# USB.net
KiCad netlist of a schematic drawn in Altium Designer
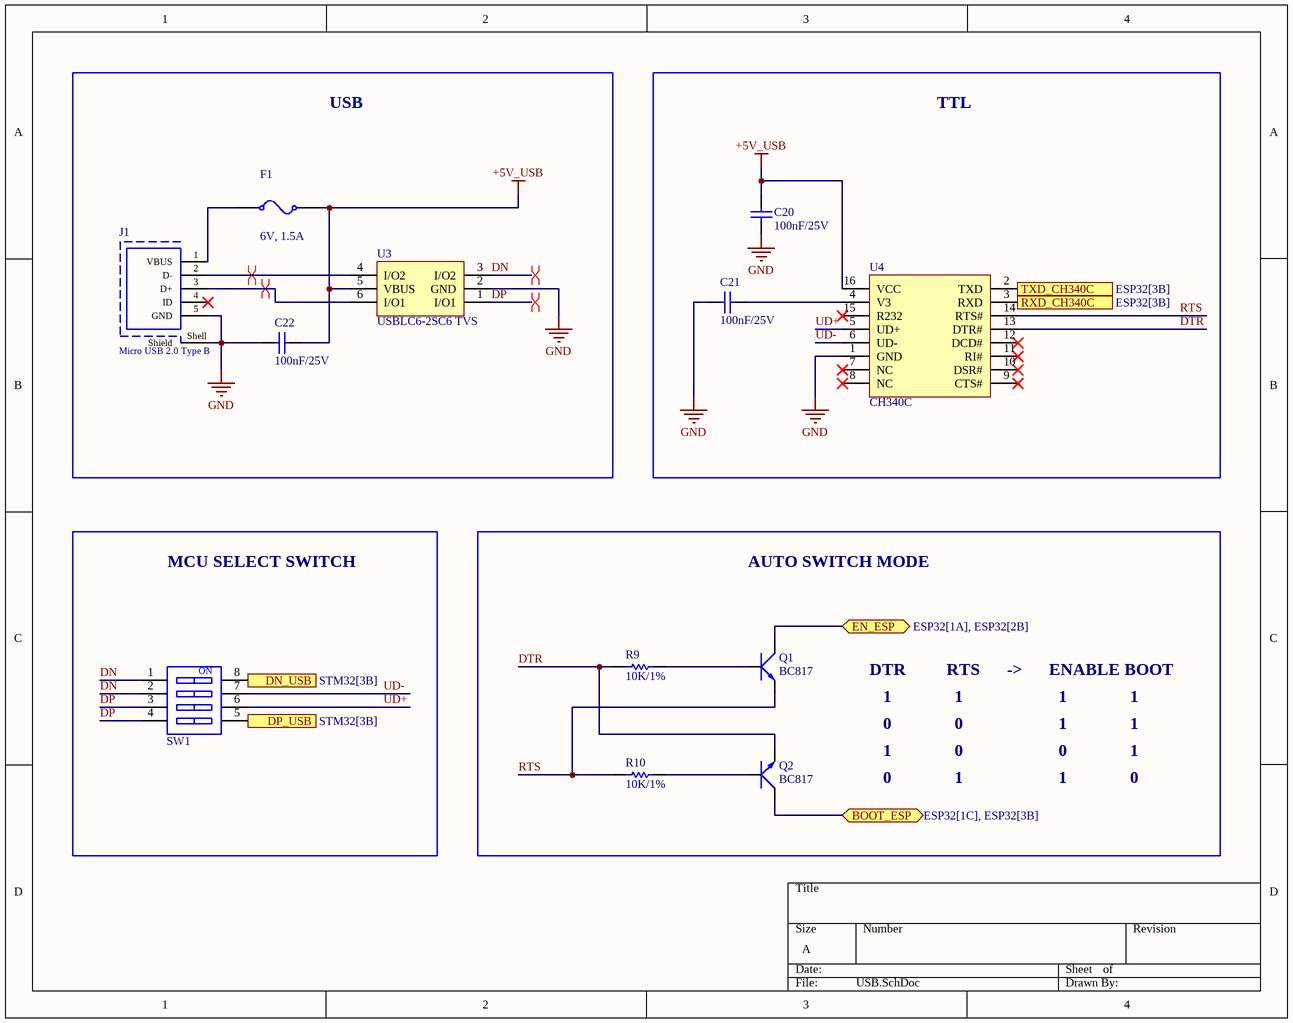
[diagram p0: USB.SchDoc]

(export (version "E")
  (design (tool "Eeschema 10.0.6"))
  (components
    (comp (ref "C20")
      (value "100nF/25V")
      (footprint "CAP-SM-0805")
      (description "Capacitor")
      (fields (field (name "Comment") "Cap Non-Pol SMD"))
      (libsource (lib "PIF_Library") (part "Cap Non-Pol SMD"))
    )
    (comp (ref "C21")
      (value "100nF/25V")
      (footprint "CAP-SM-0805")
      (description "Capacitor")
      (fields (field (name "Comment") "Cap Non-Pol SMD"))
      (libsource (lib "PIF_Library") (part "Cap Non-Pol SMD"))
    )
    (comp (ref "C22")
      (value "100nF/25V")
      (footprint "CAP-SM-0805")
      (description "Capacitor")
      (fields (field (name "Comment") "Cap Non-Pol SMD"))
      (libsource (lib "PIF_Library") (part "Cap Non-Pol SMD"))
    )
    (comp (ref "F1")
      (value "6V, 1.5A")
      (footprint "Fuse_SMD_1812")
      (description "Resettable Fuse, Size 1812, 24V, 1.5A")
      (fields (field (name "MANUFACTURER") "Littelfuse"))
      (libsource (lib "Altium_Fuse") (part "061812150024"))
    )
    (comp (ref "J1")
      (value "Micro USB 2.0 Type B")
      (footprint "629105150521")
      (description "Micro USB 2.0 Type B Receptacle WR-COM, Horizontal, SMT, with Pegs, High Current at Pin 1 & Pin 5")
      (fields (field (name "PART NUMBER") "629105150521") (field (name "PUBLISHER") "Wurth Elektronik"))
      (libsource (lib "Altium_USB") (part "629105150521"))
    )
    (comp (ref "Q1")
      (value "BC817")
      (footprint "SOT-23")
      (description "SOT-23 - C8658")
      (libsource (lib "Altium_Lib_by_KhueNguyenCreator") (part "Trans BC817"))
    )
    (comp (ref "Q2")
      (value "BC817")
      (footprint "SOT-23")
      (description "SOT-23 - C8658")
      (libsource (lib "Altium_Lib_by_KhueNguyenCreator") (part "Trans BC817"))
    )
    (comp (ref "R9")
      (value "10K/1%")
      (footprint "RES-SM-0805")
      (description "Resistor")
      (fields (field (name "Comment") "RESISTOR SMD"))
      (libsource (lib "PIF_Library") (part "RESISTOR SMD"))
    )
    (comp (ref "R10")
      (value "10K/1%")
      (footprint "RES-SM-0805")
      (description "Resistor")
      (fields (field (name "Comment") "RESISTOR SMD"))
      (libsource (lib "PIF_Library") (part "RESISTOR SMD"))
    )
    (comp (ref "SW1")
      (value "418117270904")
      (footprint "418117270904")
      (description "WS-DITV Compact THT Dip Switch, Raised Actuator, pitch 2.54mm, 4p")
      (fields (field (name "MANUFACTURER") "Wurth Elektronik"))
      (libsource (lib "Altium_Button") (part "418117270904"))
    )
    (comp (ref "U3")
      (value "USBLC6-2SC6 TVS")
      (footprint "SOT23-6")
      (description "Oscillator, Silicon IC 3.81Hz ~ 1MHz TSOT-23-6")
      (fields
        (field (name "MANUFACTURER") "Linear Technology/Analog Devices")
        (field (name "MANUFACTURER PART NUMBER") "LTC6992IS6-1")
      )
      (libsource (lib "Altium_Lib_by_KhueNguyenCreator") (part "IC_LTC6992IS6-1"))
    )
    (comp (ref "U4")
      (value "CH340C")
      (footprint "SOIC16_50_284_25X90_SMT")
      (description "USB Bridge, USB to UART USB 2.0 UART Interface")
      (fields (field (name "MANUFACTURER") "Olimex"))
      (libsource (lib "Altium_Lib_by_KhueNguyenCreator") (part "CH340C"))
    )
  )
  (nets
    (net (code "1") (name "+5V_USB") (class "Default")
      (node (ref "C20") (pin "1") (pinfunction "1_1") (pintype "passive"))
      (node (ref "C22") (pin "2") (pinfunction "2_2") (pintype "passive"))
      (node (ref "F1") (pin "1") (pinfunction "1_1") (pintype "passive"))
      (node (ref "U3") (pin "5") (pinfunction "VBUS_5") (pintype "passive"))
      (node (ref "U4") (pin "16") (pinfunction "VCC_16") (pintype "passive"))
    )
    (net (code "2") (name "/BOOT_ESP") (class "Default")
      (node (ref "Q2") (pin "3") (pinfunction "C_3") (pintype "passive"))
    )
    (net (code "3") (name "/DN") (class "Default")
      (node (ref "SW1") (pin "1") (pinfunction "1_1") (pintype "passive"))
      (node (ref "SW1") (pin "2") (pinfunction "2_2") (pintype "passive"))
      (node (ref "U3") (pin "3") (pinfunction "I/O2_3") (pintype "passive"))
    )
    (net (code "4") (name "/DN_USB") (class "Default")
      (node (ref "SW1") (pin "8") (pinfunction "8_8") (pintype "passive"))
    )
    (net (code "5") (name "/DP") (class "Default")
      (node (ref "SW1") (pin "3") (pinfunction "3_3") (pintype "passive"))
      (node (ref "SW1") (pin "4") (pinfunction "4_4") (pintype "passive"))
      (node (ref "U3") (pin "1") (pinfunction "I/O1_1") (pintype "passive"))
    )
    (net (code "6") (name "/DP_USB") (class "Default")
      (node (ref "SW1") (pin "5") (pinfunction "5_5") (pintype "passive"))
    )
    (net (code "7") (name "/DTR") (class "Default")
      (node (ref "Q2") (pin "2") (pinfunction "E_2") (pintype "passive"))
      (node (ref "R9") (pin "1") (pinfunction "1_1") (pintype "passive"))
      (node (ref "U4") (pin "13") (pinfunction "DTR#_13") (pintype "passive"))
    )
    (net (code "8") (name "/EN_ESP") (class "Default")
      (node (ref "Q1") (pin "3") (pinfunction "C_3") (pintype "passive"))
    )
    (net (code "9") (name "/RTS") (class "Default")
      (node (ref "Q1") (pin "2") (pinfunction "E_2") (pintype "passive"))
      (node (ref "R10") (pin "1") (pinfunction "1_1") (pintype "passive"))
      (node (ref "U4") (pin "14") (pinfunction "RTS#_14") (pintype "passive"))
    )
    (net (code "10") (name "/RXD_CH340C") (class "Default")
      (node (ref "U4") (pin "3") (pinfunction "RXD_3") (pintype "passive"))
    )
    (net (code "11") (name "/TXD_CH340C") (class "Default")
      (node (ref "U4") (pin "2") (pinfunction "TXD_2") (pintype "passive"))
    )
    (net (code "12") (name "/UD+") (class "Default")
      (node (ref "SW1") (pin "6") (pinfunction "6_6") (pintype "passive"))
      (node (ref "U4") (pin "5") (pinfunction "UD+_5") (pintype "passive"))
    )
    (net (code "13") (name "/UD-") (class "Default")
      (node (ref "SW1") (pin "7") (pinfunction "7_7") (pintype "passive"))
      (node (ref "U4") (pin "6") (pinfunction "UD-_6") (pintype "passive"))
    )
    (net (code "14") (name "GND") (class "Default")
      (node (ref "C20") (pin "2") (pinfunction "2_2") (pintype "passive"))
      (node (ref "C21") (pin "2") (pinfunction "2_2") (pintype "passive"))
      (node (ref "C22") (pin "1") (pinfunction "1_1") (pintype "passive"))
      (node (ref "J1") (pin "5") (pinfunction "GND_5") (pintype "passive"))
      (node (ref "J1") (pin "Shell") (pinfunction "Shield_Shell") (pintype "passive"))
      (node (ref "U3") (pin "2") (pinfunction "GND_2") (pintype "passive"))
      (node (ref "U4") (pin "1") (pinfunction "GND_1") (pintype "passive"))
    )
    (net (code "15") (name "Net-(J1-D+)") (class "Default")
      (node (ref "J1") (pin "3") (pinfunction "D+_3") (pintype "passive"))
      (node (ref "U3") (pin "6") (pinfunction "I/O1_6") (pintype "passive"))
    )
    (net (code "16") (name "Net-(J1-D-)") (class "Default")
      (node (ref "J1") (pin "2") (pinfunction "D-_2") (pintype "passive"))
      (node (ref "U3") (pin "4") (pinfunction "I/O2_4") (pintype "passive"))
    )
    (net (code "17") (name "Net-(J1-VBUS)") (class "Default")
      (node (ref "F1") (pin "0") (pinfunction "0_0") (pintype "passive"))
      (node (ref "J1") (pin "1") (pinfunction "VBUS_1") (pintype "passive"))
    )
    (net (code "18") (name "Net-(Q1-B)") (class "Default")
      (node (ref "Q1") (pin "1") (pinfunction "B_1") (pintype "passive"))
      (node (ref "R9") (pin "2") (pinfunction "2_2") (pintype "passive"))
    )
    (net (code "19") (name "Net-(Q2-B)") (class "Default")
      (node (ref "Q2") (pin "1") (pinfunction "B_1") (pintype "passive"))
      (node (ref "R10") (pin "2") (pinfunction "2_2") (pintype "passive"))
    )
    (net (code "20") (name "Net-(U4-V3)") (class "Default")
      (node (ref "C21") (pin "1") (pinfunction "1_1") (pintype "passive"))
      (node (ref "U4") (pin "4") (pinfunction "V3_4") (pintype "passive"))
    )
    (net (code "21") (name "unconnected-(J1-ID-Pad4)") (class "Default")
      (node (ref "J1") (pin "4") (pinfunction "ID_4") (pintype "passive+no_connect"))
    )
    (net (code "22") (name "unconnected-(U4-CTS#-Pad9)") (class "Default")
      (node (ref "U4") (pin "9") (pinfunction "CTS#_9") (pintype "passive+no_connect"))
    )
    (net (code "23") (name "unconnected-(U4-DCD#-Pad12)") (class "Default")
      (node (ref "U4") (pin "12") (pinfunction "DCD#_12") (pintype "passive+no_connect"))
    )
    (net (code "24") (name "unconnected-(U4-DSR#-Pad10)") (class "Default")
      (node (ref "U4") (pin "10") (pinfunction "DSR#_10") (pintype "passive+no_connect"))
    )
    (net (code "25") (name "unconnected-(U4-NC-Pad7)") (class "Default")
      (node (ref "U4") (pin "7") (pinfunction "NC_7") (pintype "passive+no_connect"))
    )
    (net (code "26") (name "unconnected-(U4-NC-Pad8)") (class "Default")
      (node (ref "U4") (pin "8") (pinfunction "NC_8") (pintype "passive+no_connect"))
    )
    (net (code "27") (name "unconnected-(U4-R232-Pad15)") (class "Default")
      (node (ref "U4") (pin "15") (pinfunction "R232_15") (pintype "passive+no_connect"))
    )
    (net (code "28") (name "unconnected-(U4-RI#-Pad11)") (class "Default")
      (node (ref "U4") (pin "11") (pinfunction "RI#_11") (pintype "passive+no_connect"))
    )
  )
)
